# LaserTagTargetBoard.net
KiCad netlist of a schematic drawn in Altium Designer
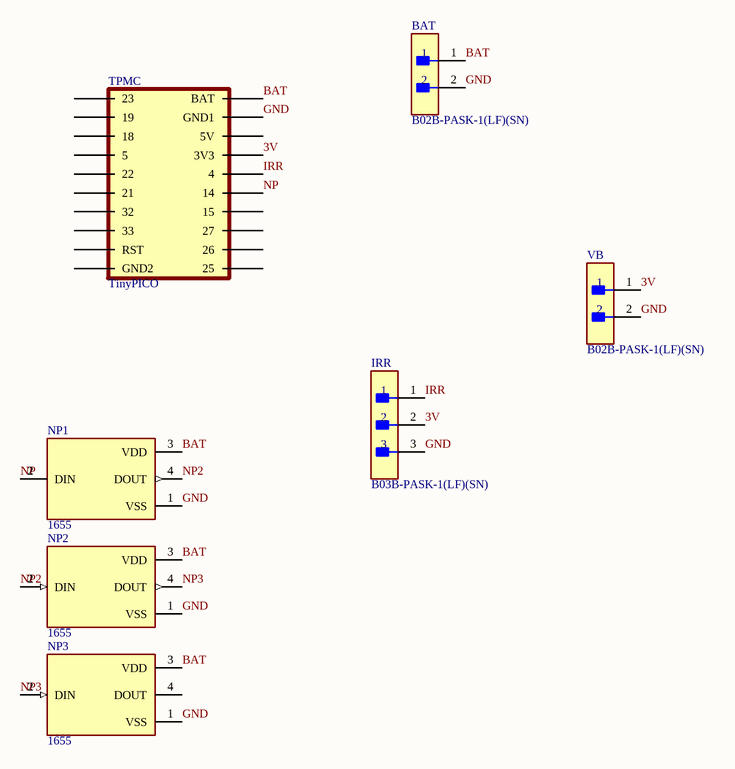
[diagram p0: LaserTagTargetBoard.SchDoc]

(export (version "E")
  (design (tool "Eeschema 10.0.6"))
  (components
    (comp (ref "BAT")
      (value "B02B-PASK-1(LF)(SN)")
      (footprint "FP-B02B-PASK-1_LF_SN-MFG")
      (description "CONN HEADER VERT 2POS 2MM")
      (libsource (lib "Altium Content Vault") (part "3bc925449376181038e59eaffc5286c"))
    )
    (comp (ref "IRR")
      (value "B03B-PASK-1(LF)(SN)")
      (footprint "FP-B03B-PASK-1_LF_SN-MFG")
      (description "CONN HEADER VERT 3POS 2MM")
      (libsource (lib "Altium Content Vault") (part "0d3f023dd272f625e17a2be33dea85f"))
    )
    (comp (ref "NP1")
      (value "1655")
      (footprint "LED_1655")
      (description "Ws2812b 5050 Rgb Led With Integrated Driver Chip Pack Of 10")
      (libsource (lib "1655") (part "1655"))
    )
    (comp (ref "NP2")
      (value "1655")
      (footprint "LED_1655")
      (description "Ws2812b 5050 Rgb Led With Integrated Driver Chip Pack Of 10")
      (libsource (lib "1655") (part "1655"))
    )
    (comp (ref "NP3")
      (value "1655")
      (footprint "LED_1655")
      (description "Ws2812b 5050 Rgb Led With Integrated Driver Chip Pack Of 10")
      (libsource (lib "1655") (part "1655"))
    )
    (comp (ref "TPMC")
      (value "TinyPICO")
      (footprint "TinyPICO")
      (libsource (lib "TinyPICO") (part "TinyPICO"))
    )
    (comp (ref "VB")
      (value "B02B-PASK-1(LF)(SN)")
      (footprint "FP-B02B-PASK-1_LF_SN-MFG")
      (description "CONN HEADER VERT 2POS 2MM")
      (libsource (lib "Altium Content Vault") (part "3bc925449376181038e59eaffc5286c"))
    )
  )
  (nets
    (net (code "1") (name "/3V") (class "Default")
      (node (ref "IRR") (pin "2") (pinfunction "2_2") (pintype "passive"))
      (node (ref "TPMC") (pin "3V3") (pinfunction "3V3_3V3") (pintype "passive"))
      (node (ref "VB") (pin "1") (pinfunction "1_1") (pintype "passive"))
    )
    (net (code "2") (name "/BAT") (class "Default")
      (node (ref "BAT") (pin "1") (pinfunction "1_1") (pintype "passive"))
      (node (ref "NP1") (pin "3") (pinfunction "VDD_3") (pintype "power_in"))
      (node (ref "NP2") (pin "3") (pinfunction "VDD_3") (pintype "power_in"))
      (node (ref "NP3") (pin "3") (pinfunction "VDD_3") (pintype "power_in"))
      (node (ref "TPMC") (pin "BAT") (pinfunction "BAT_BAT") (pintype "passive"))
    )
    (net (code "3") (name "/GND") (class "Default")
      (node (ref "BAT") (pin "2") (pinfunction "2_2") (pintype "passive"))
      (node (ref "IRR") (pin "3") (pinfunction "3_3") (pintype "passive"))
      (node (ref "NP1") (pin "1") (pinfunction "VSS_1") (pintype "power_in"))
      (node (ref "NP2") (pin "1") (pinfunction "VSS_1") (pintype "power_in"))
      (node (ref "NP3") (pin "1") (pinfunction "VSS_1") (pintype "power_in"))
      (node (ref "TPMC") (pin "GND1") (pinfunction "GND1_GND1") (pintype "passive"))
      (node (ref "VB") (pin "2") (pinfunction "2_2") (pintype "passive"))
    )
    (net (code "4") (name "/IRR") (class "Default")
      (node (ref "IRR") (pin "1") (pinfunction "1_1") (pintype "passive"))
      (node (ref "TPMC") (pin "4") (pinfunction "4_4") (pintype "passive"))
    )
    (net (code "5") (name "/NP") (class "Default")
      (node (ref "NP1") (pin "2") (pinfunction "DIN_2") (pintype "passive"))
      (node (ref "TPMC") (pin "14") (pinfunction "14_14") (pintype "passive"))
    )
    (net (code "6") (name "/NP2") (class "Default")
      (node (ref "NP1") (pin "4") (pinfunction "DOUT_4") (pintype "output"))
      (node (ref "NP2") (pin "2") (pinfunction "DIN_2") (pintype "passive"))
    )
    (net (code "7") (name "/NP3") (class "Default")
      (node (ref "NP2") (pin "4") (pinfunction "DOUT_4") (pintype "output"))
      (node (ref "NP3") (pin "2") (pinfunction "DIN_2") (pintype "passive"))
    )
    (net (code "8") (name "unconnected-(NP3-DOUT-Pad4)") (class "Default")
      (node (ref "NP3") (pin "4") (pinfunction "DOUT_4") (pintype "output"))
    )
    (net (code "9") (name "unconnected-(TPMC-Pad5)") (class "Default")
      (node (ref "TPMC") (pin "5") (pinfunction "5_5") (pintype "passive"))
    )
    (net (code "10") (name "unconnected-(TPMC-Pad5V)") (class "Default")
      (node (ref "TPMC") (pin "5V") (pinfunction "5V_5V") (pintype "passive"))
    )
    (net (code "11") (name "unconnected-(TPMC-Pad15)") (class "Default")
      (node (ref "TPMC") (pin "15") (pinfunction "15_15") (pintype "passive"))
    )
    (net (code "12") (name "unconnected-(TPMC-Pad18)") (class "Default")
      (node (ref "TPMC") (pin "18") (pinfunction "18_18") (pintype "passive"))
    )
    (net (code "13") (name "unconnected-(TPMC-Pad19)") (class "Default")
      (node (ref "TPMC") (pin "19") (pinfunction "19_19") (pintype "passive"))
    )
    (net (code "14") (name "unconnected-(TPMC-Pad21)") (class "Default")
      (node (ref "TPMC") (pin "21") (pinfunction "21_21") (pintype "passive"))
    )
    (net (code "15") (name "unconnected-(TPMC-Pad22)") (class "Default")
      (node (ref "TPMC") (pin "22") (pinfunction "22_22") (pintype "passive"))
    )
    (net (code "16") (name "unconnected-(TPMC-Pad23)") (class "Default")
      (node (ref "TPMC") (pin "23") (pinfunction "23_23") (pintype "passive"))
    )
    (net (code "17") (name "unconnected-(TPMC-Pad25)") (class "Default")
      (node (ref "TPMC") (pin "25") (pinfunction "25_25") (pintype "passive"))
    )
    (net (code "18") (name "unconnected-(TPMC-Pad26)") (class "Default")
      (node (ref "TPMC") (pin "26") (pinfunction "26_26") (pintype "passive"))
    )
    (net (code "19") (name "unconnected-(TPMC-Pad27)") (class "Default")
      (node (ref "TPMC") (pin "27") (pinfunction "27_27") (pintype "passive"))
    )
    (net (code "20") (name "unconnected-(TPMC-Pad32)") (class "Default")
      (node (ref "TPMC") (pin "32") (pinfunction "32_32") (pintype "passive"))
    )
    (net (code "21") (name "unconnected-(TPMC-Pad33)") (class "Default")
      (node (ref "TPMC") (pin "33") (pinfunction "33_33") (pintype "passive"))
    )
    (net (code "22") (name "unconnected-(TPMC-PadGND2)") (class "Default")
      (node (ref "TPMC") (pin "GND2") (pinfunction "GND2_GND2") (pintype "passive"))
    )
    (net (code "23") (name "unconnected-(TPMC-PadRST)") (class "Default")
      (node (ref "TPMC") (pin "RST") (pinfunction "RST_RST") (pintype "passive"))
    )
  )
)
